# adv_block.net
KiCad netlist of a schematic drawn in Altium Designer
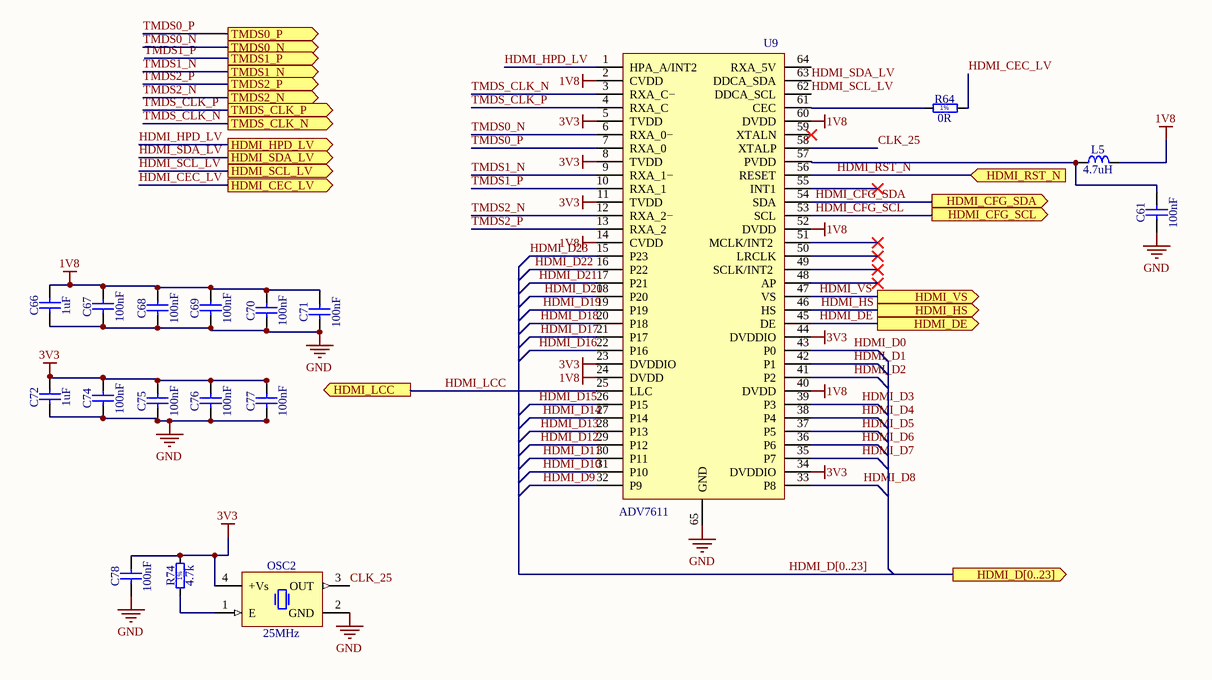
[diagram p0: adv_block.SchDoc]

(export (version "E")
  (design (tool "Eeschema 10.0.6"))
  (components
    (comp (ref "C61")
      (value "100nF")
      (footprint "CAPC1005X55N")
      (description "Non-polarised capacitor")
      (fields
        (field (name "PART NUMBER") "CC0402_100NF_16V_10%_X5R")
        (field (name "VOLTAGE") "16V")
        (field (name "AUTHOR") "CERN DEM JLC")
      )
      (libsource (lib "Capacitors") (part "Capacitor - non polarized"))
    )
    (comp (ref "C66")
      (value "1uF")
      (footprint "CAPC1005X55N")
      (description "Non-polarised capacitor")
      (fields
        (field (name "PART NUMBER") "CC0402_100NF_16V_10%_X5R")
        (field (name "VOLTAGE") "16V")
        (field (name "AUTHOR") "CERN DEM JLC")
      )
      (libsource (lib "Capacitors") (part "Capacitor - non polarized"))
    )
    (comp (ref "C67")
      (value "100nF")
      (footprint "CAPC1005X55N")
      (description "Non-polarised capacitor")
      (fields
        (field (name "PART NUMBER") "CC0402_100NF_16V_10%_X5R")
        (field (name "VOLTAGE") "16V")
        (field (name "AUTHOR") "CERN DEM JLC")
      )
      (libsource (lib "Capacitors") (part "Capacitor - non polarized"))
    )
    (comp (ref "C68")
      (value "100nF")
      (footprint "CAPC1005X55N")
      (description "Non-polarised capacitor")
      (fields
        (field (name "PART NUMBER") "CC0402_100NF_16V_10%_X5R")
        (field (name "VOLTAGE") "16V")
        (field (name "AUTHOR") "CERN DEM JLC")
      )
      (libsource (lib "Capacitors") (part "Capacitor - non polarized"))
    )
    (comp (ref "C69")
      (value "100nF")
      (footprint "CAPC1005X55N")
      (description "Non-polarised capacitor")
      (fields
        (field (name "PART NUMBER") "CC0402_100NF_16V_10%_X5R")
        (field (name "VOLTAGE") "16V")
        (field (name "AUTHOR") "CERN DEM JLC")
      )
      (libsource (lib "Capacitors") (part "Capacitor - non polarized"))
    )
    (comp (ref "C70")
      (value "100nF")
      (footprint "CAPC1005X55N")
      (description "Non-polarised capacitor")
      (fields
        (field (name "PART NUMBER") "CC0402_100NF_16V_10%_X5R")
        (field (name "VOLTAGE") "16V")
        (field (name "AUTHOR") "CERN DEM JLC")
      )
      (libsource (lib "Capacitors") (part "Capacitor - non polarized"))
    )
    (comp (ref "C71")
      (value "100nF")
      (footprint "CAPC1005X55N")
      (description "Non-polarised capacitor")
      (fields
        (field (name "PART NUMBER") "CC0402_100NF_16V_10%_X5R")
        (field (name "VOLTAGE") "16V")
        (field (name "AUTHOR") "CERN DEM JLC")
      )
      (libsource (lib "Capacitors") (part "Capacitor - non polarized"))
    )
    (comp (ref "C72")
      (value "1uF")
      (footprint "CAPC1005X55N")
      (description "Non-polarised capacitor")
      (fields
        (field (name "PART NUMBER") "CC0402_100NF_16V_10%_X5R")
        (field (name "VOLTAGE") "16V")
        (field (name "AUTHOR") "CERN DEM JLC")
      )
      (libsource (lib "Capacitors") (part "Capacitor - non polarized"))
    )
    (comp (ref "C74")
      (value "100nF")
      (footprint "CAPC1005X55N")
      (description "Non-polarised capacitor")
      (fields
        (field (name "PART NUMBER") "CC0402_100NF_16V_10%_X5R")
        (field (name "VOLTAGE") "16V")
        (field (name "AUTHOR") "CERN DEM JLC")
      )
      (libsource (lib "Capacitors") (part "Capacitor - non polarized"))
    )
    (comp (ref "C75")
      (value "100nF")
      (footprint "CAPC1005X55N")
      (description "Non-polarised capacitor")
      (fields
        (field (name "PART NUMBER") "CC0402_100NF_16V_10%_X5R")
        (field (name "VOLTAGE") "16V")
        (field (name "AUTHOR") "CERN DEM JLC")
      )
      (libsource (lib "Capacitors") (part "Capacitor - non polarized"))
    )
    (comp (ref "C76")
      (value "100nF")
      (footprint "CAPC1005X55N")
      (description "Non-polarised capacitor")
      (fields
        (field (name "PART NUMBER") "CC0402_100NF_16V_10%_X5R")
        (field (name "VOLTAGE") "16V")
        (field (name "AUTHOR") "CERN DEM JLC")
      )
      (libsource (lib "Capacitors") (part "Capacitor - non polarized"))
    )
    (comp (ref "C77")
      (value "100nF")
      (footprint "CAPC1005X55N")
      (description "Non-polarised capacitor")
      (fields
        (field (name "PART NUMBER") "CC0402_100NF_16V_10%_X5R")
        (field (name "VOLTAGE") "16V")
        (field (name "AUTHOR") "CERN DEM JLC")
      )
      (libsource (lib "Capacitors") (part "Capacitor - non polarized"))
    )
    (comp (ref "C78")
      (value "100nF")
      (footprint "CAPC1005X55N")
      (description "Non-polarised capacitor")
      (fields
        (field (name "PART NUMBER") "CC0402_100NF_16V_10%_X5R")
        (field (name "VOLTAGE") "16V")
        (field (name "AUTHOR") "CERN DEM JLC")
      )
      (libsource (lib "Capacitors") (part "Capacitor - non polarized"))
    )
    (comp (ref "L5")
      (value "4.7uH")
      (footprint "IND_MURATA_BLM31PG")
      (description "Inductor")
      (fields
        (field (name "PART NUMBER") "IND1206_MURATA_BLM31PG500SN1")
        (field (name "POWER") "3.5A")
        (field (name "AUTHOR") "CERN DEM JLC")
      )
      (libsource (lib "Inductors & Transformers") (part "Inductor"))
    )
    (comp (ref "OSC2")
      (value "25MHz")
      (footprint "OSC_IQD_CFPS-69")
      (description "Oscillator 4 pins 1=E 2=GND 3=OUT 4=+Vs")
      (fields
        (field (name "PART NUMBER") "OSC_50MHZ_IQD_LFSPXO009592")
        (field (name "MANUFACTURER") "IQD FREQUENCY PRODUCTS")
        (field (name "AUTHOR") "CERN DEM JLC")
      )
      (libsource (lib "ICs And Semiconductors") (part "Oscillator 1E 2GND 3OUT 4Vs"))
    )
    (comp (ref "R64")
      (value "0R")
      (footprint "RESC1005X40N")
      (description "Resistor - 1%")
      (fields
        (field (name "PART NUMBER") "R0402_10K_1%_0.0625W_100PPM")
        (field (name "POWER") "0.0625W")
        (field (name "AUTHOR") "CERN DEM JLC")
      )
      (libsource (lib "Resistors") (part "Resistor - 1%"))
    )
    (comp (ref "R74")
      (value "4.7k")
      (footprint "RESC1608X55N")
      (description "Resistor - 1%")
      (fields
        (field (name "PART NUMBER") "R0603_100K_1%_0.1W_100PPM")
        (field (name "POWER") "0.1W")
        (field (name "AUTHOR") "CERN DEM JLC")
      )
      (libsource (lib "Resistors") (part "Resistor - 1%"))
    )
    (comp (ref "U9")
      (value "ADV7611")
      (footprint "QFP50P1200X1200X120-65N-S415")
      (description "Low Power 165 MHz HDMI Receiver")
      (libsource (lib "lib") (part "ADV7611"))
    )
  )
  (nets
    (net (code "1") (name "/CLK_25") (class "Default")
      (node (ref "OSC2") (pin "3") (pinfunction "OUT_3") (pintype "output"))
      (node (ref "U9") (pin "58") (pinfunction "XTALP_58") (pintype "passive"))
    )
    (net (code "2") (name "/HDMI_CEC_LV") (class "Default")
      (node (ref "R64") (pin "2") (pinfunction "2_2") (pintype "passive"))
    )
    (net (code "3") (name "/HDMI_CFG_SCL") (class "Default")
      (node (ref "U9") (pin "53") (pinfunction "SCL_53") (pintype "passive"))
    )
    (net (code "4") (name "/HDMI_CFG_SDA") (class "Default")
      (node (ref "U9") (pin "54") (pinfunction "SDA_54") (pintype "passive"))
    )
    (net (code "5") (name "/HDMI_D0") (class "Default")
      (node (ref "U9") (pin "43") (pinfunction "P0_43") (pintype "passive"))
    )
    (net (code "6") (name "/HDMI_D1") (class "Default")
      (node (ref "U9") (pin "42") (pinfunction "P1_42") (pintype "passive"))
    )
    (net (code "7") (name "/HDMI_D2") (class "Default")
      (node (ref "U9") (pin "41") (pinfunction "P2_41") (pintype "passive"))
    )
    (net (code "8") (name "/HDMI_D3") (class "Default")
      (node (ref "U9") (pin "39") (pinfunction "P3_39") (pintype "passive"))
    )
    (net (code "9") (name "/HDMI_D4") (class "Default")
      (node (ref "U9") (pin "38") (pinfunction "P4_38") (pintype "passive"))
    )
    (net (code "10") (name "/HDMI_D5") (class "Default")
      (node (ref "U9") (pin "37") (pinfunction "P5_37") (pintype "passive"))
    )
    (net (code "11") (name "/HDMI_D6") (class "Default")
      (node (ref "U9") (pin "36") (pinfunction "P6_36") (pintype "passive"))
    )
    (net (code "12") (name "/HDMI_D7") (class "Default")
      (node (ref "U9") (pin "35") (pinfunction "P7_35") (pintype "passive"))
    )
    (net (code "13") (name "/HDMI_D8") (class "Default")
      (node (ref "U9") (pin "33") (pinfunction "P8_33") (pintype "passive"))
    )
    (net (code "14") (name "/HDMI_D9") (class "Default")
      (node (ref "U9") (pin "32") (pinfunction "P9_32") (pintype "passive"))
    )
    (net (code "15") (name "/HDMI_D10") (class "Default")
      (node (ref "U9") (pin "31") (pinfunction "P10_31") (pintype "passive"))
    )
    (net (code "16") (name "/HDMI_D11") (class "Default")
      (node (ref "U9") (pin "30") (pinfunction "P11_30") (pintype "passive"))
    )
    (net (code "17") (name "/HDMI_D12") (class "Default")
      (node (ref "U9") (pin "29") (pinfunction "P12_29") (pintype "passive"))
    )
    (net (code "18") (name "/HDMI_D13") (class "Default")
      (node (ref "U9") (pin "28") (pinfunction "P13_28") (pintype "passive"))
    )
    (net (code "19") (name "/HDMI_D14") (class "Default")
      (node (ref "U9") (pin "27") (pinfunction "P14_27") (pintype "passive"))
    )
    (net (code "20") (name "/HDMI_D15") (class "Default")
      (node (ref "U9") (pin "26") (pinfunction "P15_26") (pintype "passive"))
    )
    (net (code "21") (name "/HDMI_D16") (class "Default")
      (node (ref "U9") (pin "22") (pinfunction "P16_22") (pintype "passive"))
    )
    (net (code "22") (name "/HDMI_D17") (class "Default")
      (node (ref "U9") (pin "21") (pinfunction "P17_21") (pintype "passive"))
    )
    (net (code "23") (name "/HDMI_D18") (class "Default")
      (node (ref "U9") (pin "20") (pinfunction "P18_20") (pintype "passive"))
    )
    (net (code "24") (name "/HDMI_D19") (class "Default")
      (node (ref "U9") (pin "19") (pinfunction "P19_19") (pintype "passive"))
    )
    (net (code "25") (name "/HDMI_D20") (class "Default")
      (node (ref "U9") (pin "18") (pinfunction "P20_18") (pintype "passive"))
    )
    (net (code "26") (name "/HDMI_D21") (class "Default")
      (node (ref "U9") (pin "17") (pinfunction "P21_17") (pintype "passive"))
    )
    (net (code "27") (name "/HDMI_D22") (class "Default")
      (node (ref "U9") (pin "16") (pinfunction "P22_16") (pintype "passive"))
    )
    (net (code "28") (name "/HDMI_D23") (class "Default")
      (node (ref "U9") (pin "15") (pinfunction "P23_15") (pintype "passive"))
    )
    (net (code "29") (name "/HDMI_DE") (class "Default")
      (node (ref "U9") (pin "45") (pinfunction "DE_45") (pintype "passive"))
    )
    (net (code "31") (name "/HDMI_HPD_LV") (class "Default")
      (node (ref "U9") (pin "1") (pinfunction "HPA_A/INT2_1") (pintype "passive"))
    )
    (net (code "32") (name "/HDMI_HS") (class "Default")
      (node (ref "U9") (pin "46") (pinfunction "HS_46") (pintype "passive"))
    )
    (net (code "33") (name "/HDMI_LCC") (class "Default")
      (node (ref "U9") (pin "25") (pinfunction "LLC_25") (pintype "passive"))
    )
    (net (code "34") (name "/HDMI_RST_N") (class "Default")
      (node (ref "U9") (pin "56") (pinfunction "RESET_56") (pintype "passive"))
    )
    (net (code "35") (name "/HDMI_SCL_LV") (class "Default")
      (node (ref "U9") (pin "62") (pinfunction "DDCA_SCL_62") (pintype "passive"))
    )
    (net (code "36") (name "/HDMI_SDA_LV") (class "Default")
      (node (ref "U9") (pin "63") (pinfunction "DDCA_SDA_63") (pintype "passive"))
    )
    (net (code "37") (name "/HDMI_VS") (class "Default")
      (node (ref "U9") (pin "47") (pinfunction "VS_47") (pintype "passive"))
    )
    (net (code "38") (name "/TMDS0_N") (class "Default")
      (node (ref "U9") (pin "6") (pinfunction "RXA_0−_6") (pintype "passive"))
    )
    (net (code "39") (name "/TMDS0_P") (class "Default")
      (node (ref "U9") (pin "7") (pinfunction "RXA_0_7") (pintype "passive"))
    )
    (net (code "40") (name "/TMDS1_N") (class "Default")
      (node (ref "U9") (pin "9") (pinfunction "RXA_1−_9") (pintype "passive"))
    )
    (net (code "41") (name "/TMDS1_P") (class "Default")
      (node (ref "U9") (pin "10") (pinfunction "RXA_1_10") (pintype "passive"))
    )
    (net (code "42") (name "/TMDS2_N") (class "Default")
      (node (ref "U9") (pin "12") (pinfunction "RXA_2−_12") (pintype "passive"))
    )
    (net (code "43") (name "/TMDS2_P") (class "Default")
      (node (ref "U9") (pin "13") (pinfunction "RXA_2_13") (pintype "passive"))
    )
    (net (code "44") (name "/TMDS_CLK_N") (class "Default")
      (node (ref "U9") (pin "3") (pinfunction "RXA_C−_3") (pintype "passive"))
    )
    (net (code "45") (name "/TMDS_CLK_P") (class "Default")
      (node (ref "U9") (pin "4") (pinfunction "RXA_C_4") (pintype "passive"))
    )
    (net (code "46") (name "1V8") (class "Default")
      (node (ref "C66") (pin "2") (pinfunction "2_2") (pintype "passive"))
      (node (ref "C67") (pin "2") (pinfunction "2_2") (pintype "passive"))
      (node (ref "C68") (pin "2") (pinfunction "2_2") (pintype "passive"))
      (node (ref "C69") (pin "2") (pinfunction "2_2") (pintype "passive"))
      (node (ref "C70") (pin "2") (pinfunction "2_2") (pintype "passive"))
      (node (ref "C71") (pin "2") (pinfunction "2_2") (pintype "passive"))
      (node (ref "L5") (pin "2") (pinfunction "2_2") (pintype "passive"))
      (node (ref "U9") (pin "14") (pinfunction "CVDD_14") (pintype "passive"))
      (node (ref "U9") (pin "2") (pinfunction "CVDD_2") (pintype "passive"))
      (node (ref "U9") (pin "24") (pinfunction "DVDD_24") (pintype "passive"))
      (node (ref "U9") (pin "40") (pinfunction "DVDD_40") (pintype "passive"))
      (node (ref "U9") (pin "52") (pinfunction "DVDD_52") (pintype "passive"))
      (node (ref "U9") (pin "60") (pinfunction "DVDD_60") (pintype "passive"))
    )
    (net (code "47") (name "3V3") (class "Default")
      (node (ref "C72") (pin "2") (pinfunction "2_2") (pintype "passive"))
      (node (ref "C74") (pin "2") (pinfunction "2_2") (pintype "passive"))
      (node (ref "C75") (pin "2") (pinfunction "2_2") (pintype "passive"))
      (node (ref "C76") (pin "2") (pinfunction "2_2") (pintype "passive"))
      (node (ref "C77") (pin "2") (pinfunction "2_2") (pintype "passive"))
      (node (ref "C78") (pin "2") (pinfunction "2_2") (pintype "passive"))
      (node (ref "OSC2") (pin "4") (pinfunction "+Vs_4") (pintype "power_in"))
      (node (ref "R74") (pin "2") (pinfunction "2_2") (pintype "passive"))
      (node (ref "U9") (pin "11") (pinfunction "TVDD_11") (pintype "passive"))
      (node (ref "U9") (pin "23") (pinfunction "DVDDIO_23") (pintype "passive"))
      (node (ref "U9") (pin "34") (pinfunction "DVDDIO_34") (pintype "passive"))
      (node (ref "U9") (pin "44") (pinfunction "DVDDIO_44") (pintype "passive"))
      (node (ref "U9") (pin "5") (pinfunction "TVDD_5") (pintype "passive"))
      (node (ref "U9") (pin "8") (pinfunction "TVDD_8") (pintype "passive"))
    )
    (net (code "48") (name "GND") (class "Default")
      (node (ref "C61") (pin "1") (pinfunction "1_1") (pintype "passive"))
      (node (ref "C66") (pin "1") (pinfunction "1_1") (pintype "passive"))
      (node (ref "C67") (pin "1") (pinfunction "1_1") (pintype "passive"))
      (node (ref "C68") (pin "1") (pinfunction "1_1") (pintype "passive"))
      (node (ref "C69") (pin "1") (pinfunction "1_1") (pintype "passive"))
      (node (ref "C70") (pin "1") (pinfunction "1_1") (pintype "passive"))
      (node (ref "C71") (pin "1") (pinfunction "1_1") (pintype "passive"))
      (node (ref "C72") (pin "1") (pinfunction "1_1") (pintype "passive"))
      (node (ref "C74") (pin "1") (pinfunction "1_1") (pintype "passive"))
      (node (ref "C75") (pin "1") (pinfunction "1_1") (pintype "passive"))
      (node (ref "C76") (pin "1") (pinfunction "1_1") (pintype "passive"))
      (node (ref "C77") (pin "1") (pinfunction "1_1") (pintype "passive"))
      (node (ref "C78") (pin "1") (pinfunction "1_1") (pintype "passive"))
      (node (ref "OSC2") (pin "2") (pinfunction "GND_2") (pintype "power_in"))
      (node (ref "U9") (pin "65") (pinfunction "GND_65") (pintype "passive"))
    )
    (net (code "49") (name "Net-(OSC2-E)") (class "Default")
      (node (ref "OSC2") (pin "1") (pinfunction "E_1") (pintype "input"))
      (node (ref "R74") (pin "1") (pinfunction "1_1") (pintype "passive"))
    )
    (net (code "50") (name "Net-(U9-CEC)") (class "Default")
      (node (ref "R64") (pin "1") (pinfunction "1_1") (pintype "passive"))
      (node (ref "U9") (pin "61") (pinfunction "CEC_61") (pintype "passive"))
    )
    (net (code "51") (name "Net-(U9-PVDD)") (class "Default")
      (node (ref "C61") (pin "2") (pinfunction "2_2") (pintype "passive"))
      (node (ref "L5") (pin "1") (pinfunction "1_1") (pintype "passive"))
      (node (ref "U9") (pin "57") (pinfunction "PVDD_57") (pintype "passive"))
    )
    (net (code "52") (name "unconnected-(U9-AP-Pad48)") (class "Default")
      (node (ref "U9") (pin "48") (pinfunction "AP_48") (pintype "passive+no_connect"))
    )
    (net (code "53") (name "unconnected-(U9-INT1-Pad55)") (class "Default")
      (node (ref "U9") (pin "55") (pinfunction "INT1_55") (pintype "passive+no_connect"))
    )
    (net (code "54") (name "unconnected-(U9-LRCLK-Pad50)") (class "Default")
      (node (ref "U9") (pin "50") (pinfunction "LRCLK_50") (pintype "passive+no_connect"))
    )
    (net (code "55") (name "unconnected-(U9-MCLK{slash}INT2-Pad51)") (class "Default")
      (node (ref "U9") (pin "51") (pinfunction "MCLK/INT2_51") (pintype "passive+no_connect"))
    )
    (net (code "56") (name "unconnected-(U9-RXA_5V-Pad64)") (class "Default")
      (node (ref "U9") (pin "64") (pinfunction "RXA_5V_64") (pintype "passive"))
    )
    (net (code "57") (name "unconnected-(U9-SCLK{slash}INT2-Pad49)") (class "Default")
      (node (ref "U9") (pin "49") (pinfunction "SCLK/INT2_49") (pintype "passive+no_connect"))
    )
    (net (code "58") (name "unconnected-(U9-XTALN-Pad59)") (class "Default")
      (node (ref "U9") (pin "59") (pinfunction "XTALN_59") (pintype "passive+no_connect"))
    )
  )
)
